# Pi_CPU_002.net
KiCad netlist of a schematic drawn in EAGLE
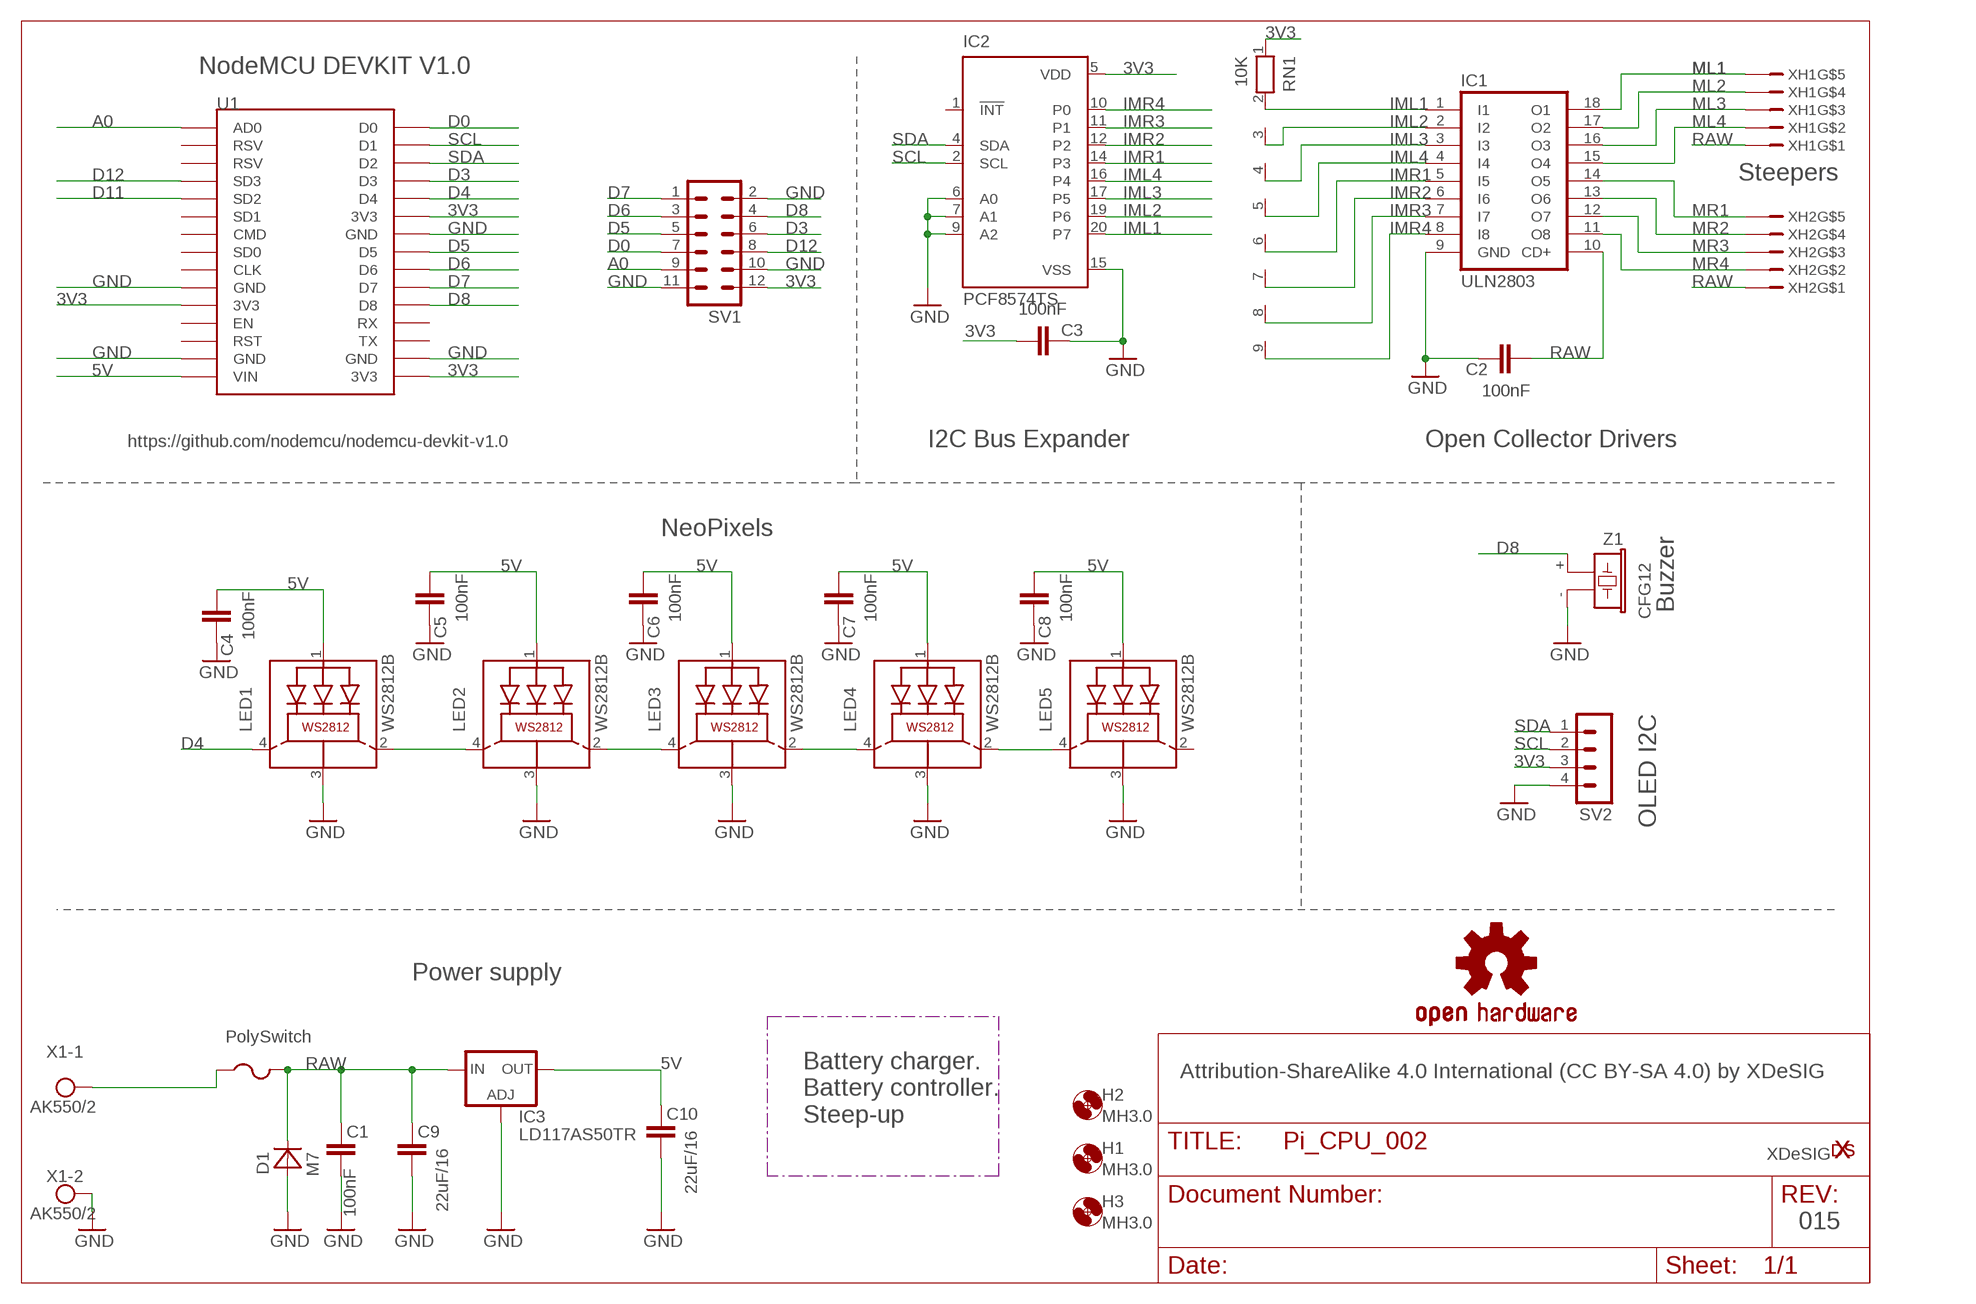
[diagram p0: schematic, sheet 1]

(export (version "E")
  (design (tool "Eeschema 10.0.6"))
  (components
    (comp (ref "C1")
      (value "100nF")
      (footprint "eagle-import:C0603K")
      (libsource (lib "eagle-import") (part "C-EUC0603K"))
    )
    (comp (ref "C2")
      (value "100nF")
      (footprint "eagle-import:C0603K")
      (libsource (lib "eagle-import") (part "C-EUC0603K"))
    )
    (comp (ref "C3")
      (value "100nF")
      (footprint "eagle-import:C0603K")
      (libsource (lib "eagle-import") (part "C-EUC0603K"))
    )
    (comp (ref "C4")
      (value "100nF")
      (footprint "eagle-import:C0603K")
      (libsource (lib "eagle-import") (part "C-EUC0603K"))
    )
    (comp (ref "C5")
      (value "100nF")
      (footprint "eagle-import:C0603K")
      (libsource (lib "eagle-import") (part "C-EUC0603K"))
    )
    (comp (ref "C6")
      (value "100nF")
      (footprint "eagle-import:C0603K")
      (libsource (lib "eagle-import") (part "C-EUC0603K"))
    )
    (comp (ref "C7")
      (value "100nF")
      (footprint "eagle-import:C0603K")
      (libsource (lib "eagle-import") (part "C-EUC0603K"))
    )
    (comp (ref "C8")
      (value "100nF")
      (footprint "eagle-import:C0603K")
      (libsource (lib "eagle-import") (part "C-EUC0603K"))
    )
    (comp (ref "C9")
      (value "22uF/16")
      (footprint "eagle-import:C1206")
      (libsource (lib "eagle-import") (part "C-EUC1206"))
    )
    (comp (ref "C10")
      (value "22uF/16")
      (footprint "eagle-import:C1206")
      (libsource (lib "eagle-import") (part "C-EUC1206"))
    )
    (comp (ref "D1")
      (value "M7")
      (footprint "eagle-import:SMA")
      (libsource (lib "eagle-import") (part "MBRA340T3"))
    )
    (comp (ref "F1")
      (value "PolySwitch")
      (footprint "eagle-import:R1206")
      (libsource (lib "eagle-import") (part "PTCFUSE-1206"))
    )
    (comp (ref "H1")
      (value "MH3.0")
      (footprint "eagle-import:3,0")
      (libsource (lib "eagle-import") (part "MOUNT-HOLE3.0"))
    )
    (comp (ref "H2")
      (value "MH3.0")
      (footprint "eagle-import:3,0")
      (libsource (lib "eagle-import") (part "MOUNT-HOLE3.0"))
    )
    (comp (ref "H3")
      (value "MH3.0")
      (footprint "eagle-import:3,0")
      (libsource (lib "eagle-import") (part "MOUNT-HOLE3.0"))
    )
    (comp (ref "IC1")
      (value "ULN2803")
      (footprint "eagle-import:DIL18")
      (libsource (lib "eagle-import") (part "ULN2803A"))
    )
    (comp (ref "IC2")
      (value "PCF8574TS")
      (footprint "eagle-import:SSOP20")
      (fields (field (name "MPN") "PCF8574TS/3,118"))
      (libsource (lib "eagle-import") (part "PCF8574TS"))
    )
    (comp (ref "IC3")
      (value "LD117AS50TR")
      (footprint "eagle-import:SOT223")
      (libsource (lib "eagle-import") (part "LD117A?S50TR"))
    )
    (comp (ref "LED1")
      (value "WS2812B")
      (footprint "eagle-import:5050-4")
      (libsource (lib "eagle-import") (part "WS2812B"))
    )
    (comp (ref "LED2")
      (value "WS2812B")
      (footprint "eagle-import:5050-4")
      (libsource (lib "eagle-import") (part "WS2812B"))
    )
    (comp (ref "LED3")
      (value "WS2812B")
      (footprint "eagle-import:5050-4")
      (libsource (lib "eagle-import") (part "WS2812B"))
    )
    (comp (ref "LED4")
      (value "WS2812B")
      (footprint "eagle-import:5050-4")
      (libsource (lib "eagle-import") (part "WS2812B"))
    )
    (comp (ref "LED5")
      (value "WS2812B")
      (footprint "eagle-import:5050-4")
      (libsource (lib "eagle-import") (part "WS2812B"))
    )
    (comp (ref "LOGO2")
      (value "OSHW-LOGOS")
      (footprint "eagle-import:OSHW-LOGO-S")
      (libsource (lib "eagle-import") (part "OSHW-LOGOS"))
    )
    (comp (ref "RN1")
      (value "10K")
      (footprint "eagle-import:RN-9")
      (libsource (lib "eagle-import") (part "RN08"))
    )
    (comp (ref "SV1")
      (value "MA06-2")
      (footprint "eagle-import:MA06-2")
      (libsource (lib "eagle-import") (part "MA06-2"))
    )
    (comp (ref "SV2")
      (value "MA04-1")
      (footprint "eagle-import:MA04-1")
      (libsource (lib "eagle-import") (part "MA04-1"))
    )
    (comp (ref "U$13")
      (value "XDESIG_XDESIG21")
      (footprint "eagle-import:XDESIG_XDESIG")
      (libsource (lib "eagle-import") (part "XDESIG_XDESIG21"))
    )
    (comp (ref "U1")
      (value "ESP12E_DEVKIT")
      (footprint "eagle-import:ESP12E_DEVKIT")
      (libsource (lib "eagle-import") (part "ESP12E_DEVKIT"))
    )
    (comp (ref "X1")
      (value "AK550/2")
      (footprint "eagle-import:AK550_2")
      (libsource (lib "eagle-import") (part "AK550/2"))
    )
    (comp (ref "XDS1")
      (value "XDESIG")
      (footprint "eagle-import:XDESIG_CU_2")
      (libsource (lib "eagle-import") (part "XDESIG"))
    )
    (comp (ref "XH1")
      (value "B5B-XH-A")
      (footprint "eagle-import:B5B-XH-A")
      (libsource (lib "eagle-import") (part "B5B-XH-A"))
    )
    (comp (ref "XH2")
      (value "B5B-XH-A")
      (footprint "eagle-import:B5B-XH-A")
      (libsource (lib "eagle-import") (part "B5B-XH-A"))
    )
    (comp (ref "Z1")
      (value "CFG12")
      (footprint "eagle-import:F_CM12P")
      (libsource (lib "eagle-import") (part "F/CM12P"))
    )
  )
  (nets
    (net (code "1") (name "/3V3") (class "Default")
      (node (ref "C3") (pin "2") (pinfunction "2_2") (pintype "passive"))
      (node (ref "IC2") (pin "5") (pinfunction "VDD_5") (pintype "power_in"))
      (node (ref "RN1") (pin "1") (pinfunction "1_1") (pintype "passive"))
      (node (ref "SV1") (pin "12") (pinfunction "12_12") (pintype "passive"))
      (node (ref "SV2") (pin "3") (pinfunction "3_3") (pintype "passive"))
      (node (ref "U1") (pin "3V3@0") (pinfunction "3V3_3V3@0") (pintype "bidirectional"))
      (node (ref "U1") (pin "3V3@1") (pinfunction "3V3_3V3@1") (pintype "bidirectional"))
      (node (ref "U1") (pin "3V3@2") (pinfunction "3V3_3V3@2") (pintype "bidirectional"))
    )
    (net (code "2") (name "/5V") (class "Default")
      (node (ref "C10") (pin "2") (pinfunction "2_2") (pintype "passive"))
      (node (ref "C4") (pin "2") (pinfunction "2_2") (pintype "passive"))
      (node (ref "C5") (pin "2") (pinfunction "2_2") (pintype "passive"))
      (node (ref "C6") (pin "2") (pinfunction "2_2") (pintype "passive"))
      (node (ref "C7") (pin "2") (pinfunction "2_2") (pintype "passive"))
      (node (ref "C8") (pin "2") (pinfunction "2_2") (pintype "passive"))
      (node (ref "IC3") (pin "4") (pinfunction "OUT_4") (pintype "passive"))
      (node (ref "LED1") (pin "1") (pinfunction "LEDVDD_1") (pintype "power_in"))
      (node (ref "LED2") (pin "1") (pinfunction "LEDVDD_1") (pintype "power_in"))
      (node (ref "LED3") (pin "1") (pinfunction "LEDVDD_1") (pintype "power_in"))
      (node (ref "LED4") (pin "1") (pinfunction "LEDVDD_1") (pintype "power_in"))
      (node (ref "LED5") (pin "1") (pinfunction "LEDVDD_1") (pintype "power_in"))
      (node (ref "U1") (pin "VIN") (pinfunction "VIN_VIN") (pintype "bidirectional"))
    )
    (net (code "3") (name "/A0") (class "Default")
      (node (ref "SV1") (pin "9") (pinfunction "9_9") (pintype "passive"))
      (node (ref "U1") (pin "AD0") (pinfunction "AD0_AD0") (pintype "bidirectional"))
    )
    (net (code "4") (name "/D0") (class "Default")
      (node (ref "SV1") (pin "7") (pinfunction "7_7") (pintype "passive"))
      (node (ref "U1") (pin "D0") (pinfunction "D0_D0") (pintype "bidirectional"))
    )
    (net (code "5") (name "/D3") (class "Default")
      (node (ref "SV1") (pin "6") (pinfunction "6_6") (pintype "passive"))
      (node (ref "U1") (pin "D3") (pinfunction "D3_D3") (pintype "bidirectional"))
    )
    (net (code "6") (name "/D4") (class "Default")
      (node (ref "LED1") (pin "4") (pinfunction "DI_4") (pintype "input"))
      (node (ref "U1") (pin "D4") (pinfunction "D4_D4") (pintype "bidirectional"))
    )
    (net (code "7") (name "/D5") (class "Default")
      (node (ref "SV1") (pin "5") (pinfunction "5_5") (pintype "passive"))
      (node (ref "U1") (pin "D5") (pinfunction "D5_D5") (pintype "bidirectional"))
    )
    (net (code "8") (name "/D6") (class "Default")
      (node (ref "SV1") (pin "3") (pinfunction "3_3") (pintype "passive"))
      (node (ref "U1") (pin "D6") (pinfunction "D6_D6") (pintype "bidirectional"))
    )
    (net (code "9") (name "/D7") (class "Default")
      (node (ref "SV1") (pin "1") (pinfunction "1_1") (pintype "passive"))
      (node (ref "U1") (pin "D7") (pinfunction "D7_D7") (pintype "bidirectional"))
    )
    (net (code "10") (name "/D8") (class "Default")
      (node (ref "SV1") (pin "4") (pinfunction "4_4") (pintype "passive"))
      (node (ref "U1") (pin "D8") (pinfunction "D8_D8") (pintype "bidirectional"))
      (node (ref "Z1") (pin "+") (pinfunction "1_+") (pintype "passive"))
    )
    (net (code "11") (name "/D11") (class "Default")
      (node (ref "U1") (pin "SD2") (pinfunction "SD2_SD2") (pintype "bidirectional"))
    )
    (net (code "12") (name "/D12") (class "Default")
      (node (ref "SV1") (pin "8") (pinfunction "8_8") (pintype "passive"))
      (node (ref "U1") (pin "SD3") (pinfunction "SD3_SD3") (pintype "bidirectional"))
    )
    (net (code "13") (name "/IML1") (class "Default")
      (node (ref "IC1") (pin "1") (pinfunction "I1_1") (pintype "input"))
      (node (ref "IC2") (pin "20") (pinfunction "P7_20") (pintype "bidirectional"))
      (node (ref "RN1") (pin "2") (pinfunction "2_2") (pintype "passive"))
    )
    (net (code "14") (name "/IML2") (class "Default")
      (node (ref "IC1") (pin "2") (pinfunction "I2_2") (pintype "input"))
      (node (ref "IC2") (pin "19") (pinfunction "P6_19") (pintype "bidirectional"))
      (node (ref "RN1") (pin "3") (pinfunction "3_3") (pintype "passive"))
    )
    (net (code "15") (name "/IML3") (class "Default")
      (node (ref "IC1") (pin "3") (pinfunction "I3_3") (pintype "input"))
      (node (ref "IC2") (pin "17") (pinfunction "P5_17") (pintype "bidirectional"))
      (node (ref "RN1") (pin "4") (pinfunction "4_4") (pintype "passive"))
    )
    (net (code "16") (name "/IML4") (class "Default")
      (node (ref "IC1") (pin "4") (pinfunction "I4_4") (pintype "input"))
      (node (ref "IC2") (pin "16") (pinfunction "P4_16") (pintype "bidirectional"))
      (node (ref "RN1") (pin "5") (pinfunction "5_5") (pintype "passive"))
    )
    (net (code "17") (name "/IMR1") (class "Default")
      (node (ref "IC1") (pin "5") (pinfunction "I5_5") (pintype "input"))
      (node (ref "IC2") (pin "14") (pinfunction "P3_14") (pintype "bidirectional"))
      (node (ref "RN1") (pin "6") (pinfunction "6_6") (pintype "passive"))
    )
    (net (code "18") (name "/IMR2") (class "Default")
      (node (ref "IC1") (pin "6") (pinfunction "I6_6") (pintype "input"))
      (node (ref "IC2") (pin "12") (pinfunction "P2_12") (pintype "bidirectional"))
      (node (ref "RN1") (pin "7") (pinfunction "7_7") (pintype "passive"))
    )
    (net (code "19") (name "/IMR3") (class "Default")
      (node (ref "IC1") (pin "7") (pinfunction "I7_7") (pintype "input"))
      (node (ref "IC2") (pin "11") (pinfunction "P1_11") (pintype "bidirectional"))
      (node (ref "RN1") (pin "8") (pinfunction "8_8") (pintype "passive"))
    )
    (net (code "20") (name "/IMR4") (class "Default")
      (node (ref "IC1") (pin "8") (pinfunction "I8_8") (pintype "input"))
      (node (ref "IC2") (pin "10") (pinfunction "P0_10") (pintype "bidirectional"))
      (node (ref "RN1") (pin "9") (pinfunction "9_9") (pintype "passive"))
    )
    (net (code "21") (name "/ML1") (class "Default")
      (node (ref "IC1") (pin "18") (pinfunction "O1_18") (pintype "open_collector"))
      (node (ref "XH1") (pin "P$5") (pinfunction "1_P$5") (pintype "passive"))
    )
    (net (code "22") (name "/ML2") (class "Default")
      (node (ref "IC1") (pin "17") (pinfunction "O2_17") (pintype "open_collector"))
      (node (ref "XH1") (pin "P$4") (pinfunction "1_P$4") (pintype "passive"))
    )
    (net (code "23") (name "/ML3") (class "Default")
      (node (ref "IC1") (pin "16") (pinfunction "O3_16") (pintype "open_collector"))
      (node (ref "XH1") (pin "P$3") (pinfunction "1_P$3") (pintype "passive"))
    )
    (net (code "24") (name "/ML4") (class "Default")
      (node (ref "IC1") (pin "15") (pinfunction "O4_15") (pintype "open_collector"))
      (node (ref "XH1") (pin "P$2") (pinfunction "1_P$2") (pintype "passive"))
    )
    (net (code "25") (name "/MR1") (class "Default")
      (node (ref "IC1") (pin "14") (pinfunction "O5_14") (pintype "open_collector"))
      (node (ref "XH2") (pin "P$5") (pinfunction "1_P$5") (pintype "passive"))
    )
    (net (code "26") (name "/MR2") (class "Default")
      (node (ref "IC1") (pin "13") (pinfunction "O6_13") (pintype "open_collector"))
      (node (ref "XH2") (pin "P$4") (pinfunction "1_P$4") (pintype "passive"))
    )
    (net (code "27") (name "/MR3") (class "Default")
      (node (ref "IC1") (pin "12") (pinfunction "O7_12") (pintype "open_collector"))
      (node (ref "XH2") (pin "P$3") (pinfunction "1_P$3") (pintype "passive"))
    )
    (net (code "28") (name "/MR4") (class "Default")
      (node (ref "IC1") (pin "11") (pinfunction "O8_11") (pintype "open_collector"))
      (node (ref "XH2") (pin "P$2") (pinfunction "1_P$2") (pintype "passive"))
    )
    (net (code "29") (name "/RAW") (class "Default")
      (node (ref "C1") (pin "2") (pinfunction "2_2") (pintype "passive"))
      (node (ref "C2") (pin "2") (pinfunction "2_2") (pintype "passive"))
      (node (ref "C9") (pin "2") (pinfunction "2_2") (pintype "passive"))
      (node (ref "D1") (pin "C") (pinfunction "C_C") (pintype "passive"))
      (node (ref "F1") (pin "2") (pinfunction "2_2") (pintype "passive"))
      (node (ref "IC1") (pin "10") (pinfunction "CD+_10") (pintype "passive"))
      (node (ref "IC3") (pin "3") (pinfunction "IN_3") (pintype "input"))
      (node (ref "XH1") (pin "P$1") (pinfunction "1_P$1") (pintype "passive"))
      (node (ref "XH2") (pin "P$1") (pinfunction "1_P$1") (pintype "passive"))
    )
    (net (code "30") (name "/SCL") (class "Default")
      (node (ref "IC2") (pin "2") (pinfunction "SCL_2") (pintype "input"))
      (node (ref "SV2") (pin "2") (pinfunction "2_2") (pintype "passive"))
      (node (ref "U1") (pin "D1") (pinfunction "D1_D1") (pintype "bidirectional"))
    )
    (net (code "31") (name "/SDA") (class "Default")
      (node (ref "IC2") (pin "4") (pinfunction "SDA_4") (pintype "bidirectional"))
      (node (ref "SV2") (pin "1") (pinfunction "1_1") (pintype "passive"))
      (node (ref "U1") (pin "D2") (pinfunction "D2_D2") (pintype "bidirectional"))
    )
    (net (code "32") (name "GND") (class "Default")
      (node (ref "C1") (pin "1") (pinfunction "1_1") (pintype "passive"))
      (node (ref "C10") (pin "1") (pinfunction "1_1") (pintype "passive"))
      (node (ref "C2") (pin "1") (pinfunction "1_1") (pintype "passive"))
      (node (ref "C3") (pin "1") (pinfunction "1_1") (pintype "passive"))
      (node (ref "C4") (pin "1") (pinfunction "1_1") (pintype "passive"))
      (node (ref "C5") (pin "1") (pinfunction "1_1") (pintype "passive"))
      (node (ref "C6") (pin "1") (pinfunction "1_1") (pintype "passive"))
      (node (ref "C7") (pin "1") (pinfunction "1_1") (pintype "passive"))
      (node (ref "C8") (pin "1") (pinfunction "1_1") (pintype "passive"))
      (node (ref "C9") (pin "1") (pinfunction "1_1") (pintype "passive"))
      (node (ref "D1") (pin "A") (pinfunction "A_A") (pintype "passive"))
      (node (ref "IC1") (pin "9") (pinfunction "GND_9") (pintype "power_in"))
      (node (ref "IC2") (pin "15") (pinfunction "VSS_15") (pintype "power_in"))
      (node (ref "IC2") (pin "6") (pinfunction "A0_6") (pintype "input"))
      (node (ref "IC2") (pin "7") (pinfunction "A1_7") (pintype "input"))
      (node (ref "IC2") (pin "9") (pinfunction "A2_9") (pintype "input"))
      (node (ref "IC3") (pin "1") (pinfunction "ADJ_1") (pintype "input"))
      (node (ref "LED1") (pin "3") (pinfunction "GND_3") (pintype "power_in"))
      (node (ref "LED2") (pin "3") (pinfunction "GND_3") (pintype "power_in"))
      (node (ref "LED3") (pin "3") (pinfunction "GND_3") (pintype "power_in"))
      (node (ref "LED4") (pin "3") (pinfunction "GND_3") (pintype "power_in"))
      (node (ref "LED5") (pin "3") (pinfunction "GND_3") (pintype "power_in"))
      (node (ref "SV1") (pin "10") (pinfunction "10_10") (pintype "passive"))
      (node (ref "SV1") (pin "11") (pinfunction "11_11") (pintype "passive"))
      (node (ref "SV1") (pin "2") (pinfunction "2_2") (pintype "passive"))
      (node (ref "SV2") (pin "4") (pinfunction "4_4") (pintype "passive"))
      (node (ref "U1") (pin "GND@0") (pinfunction "GND_GND@0") (pintype "bidirectional"))
      (node (ref "U1") (pin "GND@1") (pinfunction "GND_GND@1") (pintype "bidirectional"))
      (node (ref "U1") (pin "GND@2") (pinfunction "GND_GND@2") (pintype "bidirectional"))
      (node (ref "U1") (pin "GND@3") (pinfunction "GND_GND@3") (pintype "bidirectional"))
      (node (ref "X1") (pin "2") (pinfunction "KL_2") (pintype "passive"))
      (node (ref "Z1") (pin "-") (pinfunction "2_-") (pintype "passive"))
    )
    (net (code "33") (name "Net-(LED1-DO)") (class "Default")
      (node (ref "LED1") (pin "2") (pinfunction "DO_2") (pintype "output"))
      (node (ref "LED2") (pin "4") (pinfunction "DI_4") (pintype "input"))
    )
    (net (code "34") (name "Net-(LED2-DO)") (class "Default")
      (node (ref "LED2") (pin "2") (pinfunction "DO_2") (pintype "output"))
      (node (ref "LED3") (pin "4") (pinfunction "DI_4") (pintype "input"))
    )
    (net (code "35") (name "Net-(LED3-DO)") (class "Default")
      (node (ref "LED3") (pin "2") (pinfunction "DO_2") (pintype "output"))
      (node (ref "LED4") (pin "4") (pinfunction "DI_4") (pintype "input"))
    )
    (net (code "36") (name "Net-(LED4-DO)") (class "Default")
      (node (ref "LED4") (pin "2") (pinfunction "DO_2") (pintype "output"))
      (node (ref "LED5") (pin "4") (pinfunction "DI_4") (pintype "input"))
    )
    (net (code "37") (name "Net-(X1A-KL)") (class "Default")
      (node (ref "F1") (pin "1") (pinfunction "1_1") (pintype "passive"))
      (node (ref "X1") (pin "1") (pinfunction "KL_1") (pintype "passive"))
    )
    (net (code "38") (name "unconnected-(IC2-~{INT}-Pad1)") (class "Default")
      (node (ref "IC2") (pin "1") (pinfunction "~{INT}_1") (pintype "output"))
    )
    (net (code "39") (name "unconnected-(LED5-DO-Pad2)") (class "Default")
      (node (ref "LED5") (pin "2") (pinfunction "DO_2") (pintype "output"))
    )
    (net (code "40") (name "unconnected-(U1-PadCLK)") (class "Default")
      (node (ref "U1") (pin "CLK") (pinfunction "CLK_CLK") (pintype "bidirectional"))
    )
    (net (code "41") (name "unconnected-(U1-PadCMD)") (class "Default")
      (node (ref "U1") (pin "CMD") (pinfunction "CMD_CMD") (pintype "bidirectional"))
    )
    (net (code "42") (name "unconnected-(U1-PadEN)") (class "Default")
      (node (ref "U1") (pin "EN") (pinfunction "EN_EN") (pintype "bidirectional"))
    )
    (net (code "43") (name "unconnected-(U1-PadRST)") (class "Default")
      (node (ref "U1") (pin "RST") (pinfunction "RST_RST") (pintype "bidirectional"))
    )
    (net (code "44") (name "unconnected-(U1-PadRX)") (class "Default")
      (node (ref "U1") (pin "RX") (pinfunction "RX_RX") (pintype "bidirectional"))
    )
    (net (code "45") (name "unconnected-(U1-PadSD0)") (class "Default")
      (node (ref "U1") (pin "SD0") (pinfunction "SD0_SD0") (pintype "bidirectional"))
    )
    (net (code "46") (name "unconnected-(U1-PadSD1)") (class "Default")
      (node (ref "U1") (pin "SD1") (pinfunction "SD1_SD1") (pintype "bidirectional"))
    )
    (net (code "47") (name "unconnected-(U1-PadTX)") (class "Default")
      (node (ref "U1") (pin "TX") (pinfunction "TX_TX") (pintype "bidirectional"))
    )
    (net (code "48") (name "unconnected-(U1-RSV-PadRSV@0)") (class "Default")
      (node (ref "U1") (pin "RSV@0") (pinfunction "RSV_RSV@0") (pintype "bidirectional"))
    )
    (net (code "49") (name "unconnected-(U1-RSV-PadRSV@1)") (class "Default")
      (node (ref "U1") (pin "RSV@1") (pinfunction "RSV_RSV@1") (pintype "bidirectional"))
    )
  )
)
